# jtag.net
KiCad netlist of a schematic drawn in Altium Designer
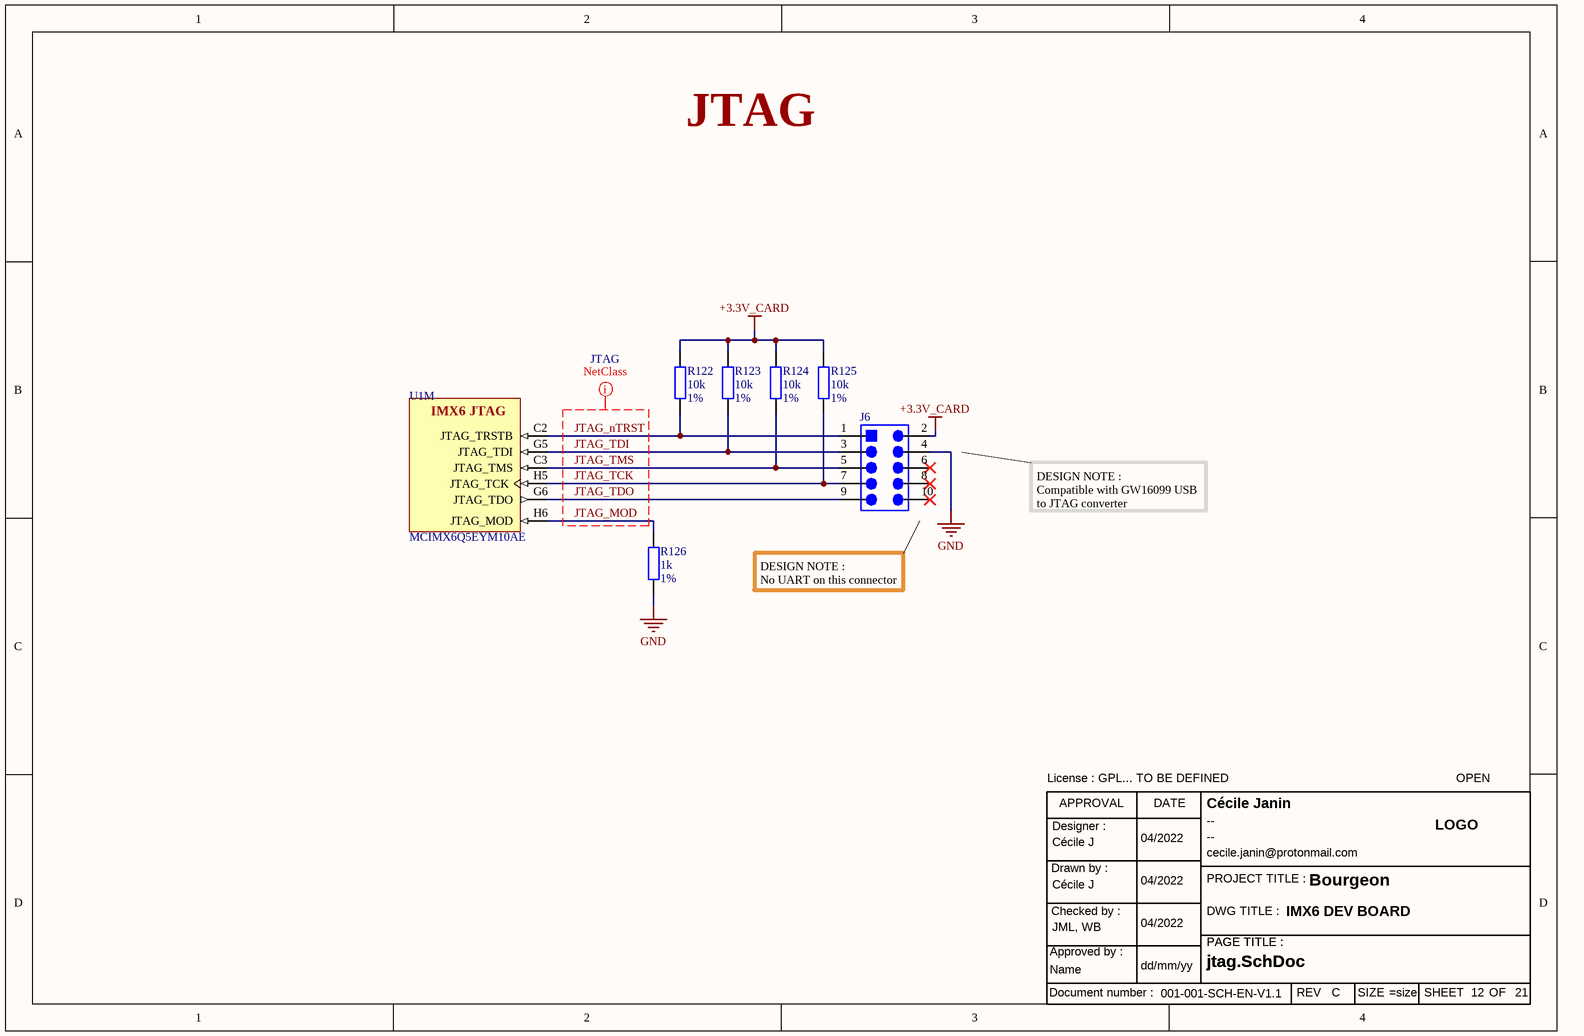
[diagram p0: jtag.SchDoc]

(export (version "E")
  (design (tool "Eeschema 10.0.6"))
  (components
    (comp (ref "J6")
      (value "header 2 row x10")
      (footprint "header 2row x10")
      (description "62131021021")
      (libsource (lib "First Board IMX6") (part "header 2 row x10"))
    )
    (comp (ref "R122")
      (value "10k")
      (footprint "Res 0402/1005")
      (description "res 10k 1% 0402")
      (fields (field (name "POURCENTAGE") "1%"))
      (libsource (lib "First Board IMX6") (part "res 10k 1%"))
    )
    (comp (ref "R123")
      (value "10k")
      (footprint "Res 0402/1005")
      (description "res 10k 1% 0402")
      (fields (field (name "POURCENTAGE") "1%"))
      (libsource (lib "First Board IMX6") (part "res 10k 1%"))
    )
    (comp (ref "R124")
      (value "10k")
      (footprint "Res 0402/1005")
      (description "res 10k 1% 0402")
      (fields (field (name "POURCENTAGE") "1%"))
      (libsource (lib "First Board IMX6") (part "res 10k 1%"))
    )
    (comp (ref "R125")
      (value "10k")
      (footprint "Res 0402/1005")
      (description "res 10k 1% 0402")
      (fields (field (name "POURCENTAGE") "1%"))
      (libsource (lib "First Board IMX6") (part "res 10k 1%"))
    )
    (comp (ref "R126")
      (value "1k")
      (footprint "Res 0402/1005")
      (description "res 1k 1% 0402")
      (fields (field (name "POURCENTAGE") "1%"))
      (libsource (lib "First Board IMX6") (part "res 1k 1%"))
    )
    (comp (ref "TB11")
      (value "Title bloc ANSI modified")
      (libsource (lib "First Board IMX6") (part "Title bloc ANSI"))
    )
    (comp (ref "U1")
      (value "MCIMX6Q5EYM10AE")
      (footprint "FRES-2197-01")
      (fields
        (field (name "PARTNUMBER") "MCIMX6Q5EYM10ACR")
        (field (name "MANUFACTURER") "Freescale Semiconductor")
      )
      (libsource (lib "First Board IMX6") (part "IMX6Q5EYM10AE"))
    )
  )
  (nets
    (net (code "1") (name "+3.3V_CARD") (class "Default")
      (node (ref "J6") (pin "2") (pintype "passive"))
      (node (ref "R122") (pin "2") (pintype "passive"))
      (node (ref "R123") (pin "2") (pintype "passive"))
      (node (ref "R124") (pin "2") (pintype "passive"))
      (node (ref "R125") (pin "2") (pintype "passive"))
    )
    (net (code "2") (name "/JTAG_MOD") (class "Default")
      (node (ref "R126") (pin "2") (pintype "passive"))
      (node (ref "U1") (pin "H6") (pinfunction "JTAG_MOD_H6") (pintype "input"))
    )
    (net (code "3") (name "/JTAG_TCK") (class "Default")
      (node (ref "J6") (pin "7") (pintype "passive"))
      (node (ref "R125") (pin "1") (pintype "passive"))
      (node (ref "U1") (pin "H5") (pinfunction "JTAG_TCK_H5") (pintype "input"))
    )
    (net (code "4") (name "/JTAG_TDI") (class "Default")
      (node (ref "J6") (pin "3") (pintype "passive"))
      (node (ref "R123") (pin "1") (pintype "passive"))
      (node (ref "U1") (pin "G5") (pinfunction "JTAG_TDI_G5") (pintype "input"))
    )
    (net (code "5") (name "/JTAG_TDO") (class "Default")
      (node (ref "J6") (pin "9") (pintype "passive"))
      (node (ref "U1") (pin "G6") (pinfunction "JTAG_TDO_G6") (pintype "output"))
    )
    (net (code "6") (name "/JTAG_TMS") (class "Default")
      (node (ref "J6") (pin "5") (pintype "passive"))
      (node (ref "R124") (pin "1") (pintype "passive"))
      (node (ref "U1") (pin "C3") (pinfunction "JTAG_TMS_C3") (pintype "input"))
    )
    (net (code "7") (name "/JTAG_nTRST") (class "Default")
      (node (ref "J6") (pin "1") (pintype "passive"))
      (node (ref "R122") (pin "1") (pintype "passive"))
      (node (ref "U1") (pin "C2") (pinfunction "JTAG_TRSTB_C2") (pintype "input"))
    )
    (net (code "8") (name "GND") (class "Default")
      (node (ref "J6") (pin "4") (pintype "passive"))
      (node (ref "R126") (pin "1") (pintype "passive"))
    )
    (net (code "9") (name "unconnected-(J6-Pad6)") (class "Default")
      (node (ref "J6") (pin "6") (pintype "passive+no_connect"))
    )
    (net (code "10") (name "unconnected-(J6-Pad8)") (class "Default")
      (node (ref "J6") (pin "8") (pintype "passive+no_connect"))
    )
    (net (code "11") (name "unconnected-(J6-Pad10)") (class "Default")
      (node (ref "J6") (pin "10") (pintype "passive+no_connect"))
    )
  )
)
